# DONGLE01.net
KiCad netlist of a schematic drawn in Altium Designer
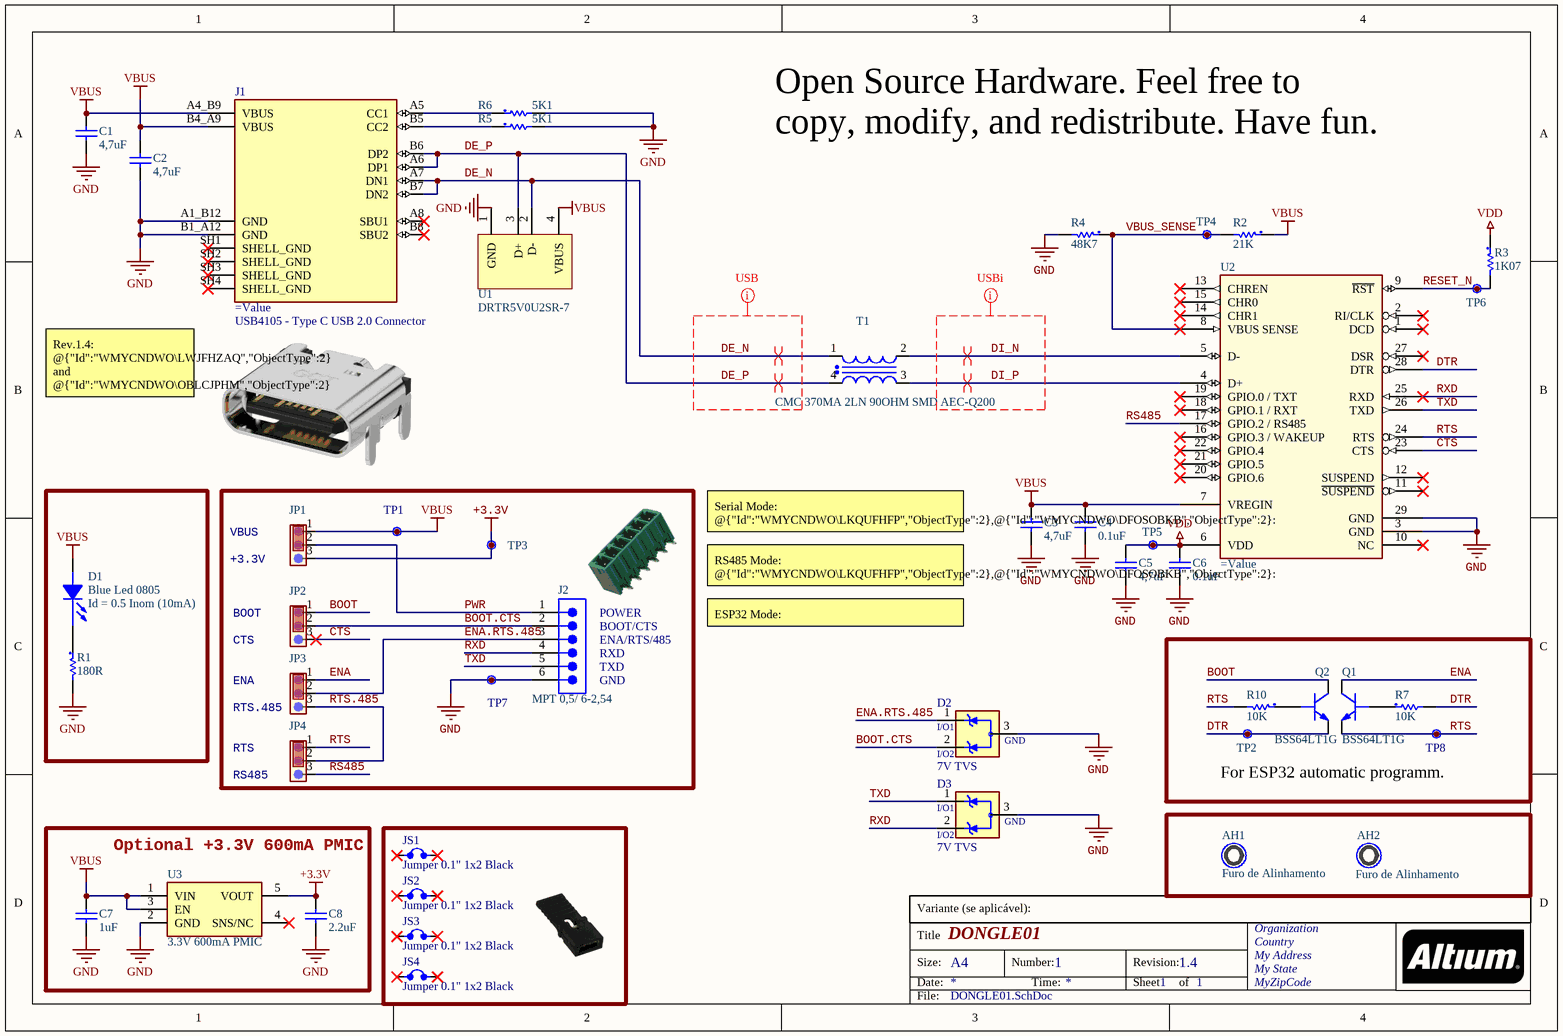
[diagram p0: DONGLE01.SchDoc]

(export (version "E")
  (design (tool "Eeschema 10.0.6"))
  (components
    (comp (ref "AH1")
      (value "Furo de Alinhamento")
      (footprint "AH_2.0MMD")
      (libsource (lib "My_Library") (part "Aligment Hole M2"))
    )
    (comp (ref "AH2")
      (value "Furo de Alinhamento")
      (footprint "AH_2.0MMD")
      (libsource (lib "My_Library") (part "Aligment Hole M2"))
    )
    (comp (ref "C1")
      (value "4,7uF")
      (footprint "C0805")
      (description "4.7 µF ±5% 25V Capacitor de cerâmica X7R 0805 (métrico 2012)")
      (fields (field (name "MANUFACTURER") "KEMET"))
      (libsource (lib "My_Library") (part "CAP"))
    )
    (comp (ref "C2")
      (value "4,7uF")
      (footprint "C0805")
      (description "4.7 µF ±5% 25V Capacitor de cerâmica X7R 0805 (métrico 2012)")
      (fields (field (name "MANUFACTURER") "KEMET"))
      (libsource (lib "My_Library") (part "CAP"))
    )
    (comp (ref "C3")
      (value "4,7uF")
      (footprint "C0805")
      (description "4.7 µF ±5% 25V Capacitor de cerâmica X7R 0805 (métrico 2012)")
      (fields (field (name "MANUFACTURER") "KEMET"))
      (libsource (lib "My_Library") (part "CAP"))
    )
    (comp (ref "C4")
      (value "0.1uF")
      (footprint "C0805")
      (description "0.1 µF ±10% 100V Ceramic Capacitor X7R 0805 (2012 Metric)")
      (fields (field (name "MANUFACTURER") "Murata Electronics"))
      (libsource (lib "My_Library") (part "CAP"))
    )
    (comp (ref "C5")
      (value "4,7uF")
      (footprint "C0805")
      (description "4.7 µF ±5% 25V Capacitor de cerâmica X7R 0805 (métrico 2012)")
      (fields (field (name "MANUFACTURER") "KEMET"))
      (libsource (lib "My_Library") (part "CAP"))
    )
    (comp (ref "C6")
      (value "0.1uF")
      (footprint "C0805")
      (description "0.1 µF ±10% 100V Ceramic Capacitor X7R 0805 (2012 Metric)")
      (fields (field (name "MANUFACTURER") "Murata Electronics"))
      (libsource (lib "My_Library") (part "CAP"))
    )
    (comp (ref "C7")
      (value "1uF")
      (footprint "C0805")
      (description "1 µF ±5% 16V Ceramic Capacitor X7R 0805 (2012 Metric)")
      (fields (field (name "MANUFACTURER") "KEMET"))
      (libsource (lib "My_Library") (part "CAP"))
    )
    (comp (ref "C8")
      (value "2.2uF")
      (footprint "C0805")
      (description "2.2 µF ±5% 16V Ceramic Capacitor X7R 0805 (2012 Metric)")
      (fields (field (name "MANUFACTURER") "KEMET"))
      (libsource (lib "My_Library") (part "CAP"))
    )
    (comp (ref "D1")
      (value "Blue Led 0805")
      (footprint "LED 0805")
      (description "Blue 470nm LED Indication - Discrete 3.2V 0805 (2012 Metric)")
      (fields (field (name "MANUFACTURER") "Würth Elektronik") (field (name "INFO") "Id = 0.5 Inom (10mA)"))
      (libsource (lib "My_Library") (part "LED GREEN 0805"))
    )
    (comp (ref "D2")
      (value "7V TVS")
      (footprint "WE-TVS_SOT23-3L")
      (description "7V Clamp 15A (8/20µs) Ipp Tvs Diode Surface Mount SOT-23-3")
      (fields (field (name "MANUFACTURER") "Würth Elektronik"))
      (libsource (lib "My_Library") (part "WE-TVS_SOT23-3L_824021"))
    )
    (comp (ref "D3")
      (value "7V TVS")
      (footprint "WE-TVS_SOT23-3L")
      (description "7V Clamp 15A (8/20µs) Ipp Tvs Diode Surface Mount SOT-23-3")
      (fields (field (name "MANUFACTURER") "Würth Elektronik"))
      (libsource (lib "My_Library") (part "WE-TVS_SOT23-3L_824021"))
    )
    (comp (ref "J1")
      (value "~")
      (footprint "GCT_USB4105-GF-A-060")
      (fields
        (field (name "INFO") "USB4105 - Type C USB 2.0 Connector")
        (field (name "MANUFACTURER") "Global Connector Technology")
      )
      (libsource (lib "My_Library") (part "USB4105-GF-A-060"))
    )
    (comp (ref "J2")
      (value "MPT 0,5/ 6-2,54")
      (footprint "1725698")
      (description "6 Position Wire to Board Terminal Block Horizontal with Board 0.100\" (2.54mm) Through Hole")
      (fields (field (name "MANUFACTURER") "Phoenix Contact"))
      (libsource (lib "691101710002_Altium_WR-TBL_rev23c") (part "691322110006"))
    )
    (comp (ref "JP1")
      (value "Header 3 Pin")
      (footprint "JMP-3-PTH-180")
      (description "3 Pin Jumper")
      (fields (field (name "MANUFACTURER") "Würth Elektronik"))
      (libsource (lib "My_Library") (part "Jumper 3"))
    )
    (comp (ref "JP2")
      (value "Header 3 Pin")
      (footprint "JMP-3-PTH-180")
      (description "3 Pin Jumper")
      (fields (field (name "MANUFACTURER") "Würth Elektronik"))
      (libsource (lib "My_Library") (part "Jumper 3"))
    )
    (comp (ref "JP3")
      (value "Header 3 Pin")
      (footprint "JMP-3-PTH-180")
      (description "3 Pin Jumper")
      (fields (field (name "MANUFACTURER") "Würth Elektronik"))
      (libsource (lib "My_Library") (part "Jumper 3"))
    )
    (comp (ref "JP4")
      (value "Header 3 Pin")
      (footprint "JMP-3-PTH-180")
      (description "3 Pin Jumper")
      (fields (field (name "MANUFACTURER") "Würth Elektronik"))
      (libsource (lib "My_Library") (part "Jumper 3"))
    )
    (comp (ref "JS1")
      (value "Jumper 0.1\" 1x2 Black")
      (description "2 (1 x 2) Position Shunt Connector Open Top, Grip 0.100\" (2.54mm) Gold")
      (fields (field (name "MANUFACTURER") "Sullins Connector Solutions"))
      (libsource (lib "My_Library") (part "Jumper 2"))
    )
    (comp (ref "JS2")
      (value "Jumper 0.1\" 1x2 Black")
      (description "2 (1 x 2) Position Shunt Connector Open Top, Grip 0.100\" (2.54mm) Gold")
      (fields (field (name "MANUFACTURER") "Sullins Connector Solutions"))
      (libsource (lib "My_Library") (part "Jumper 2"))
    )
    (comp (ref "JS3")
      (value "Jumper 0.1\" 1x2 Black")
      (description "2 (1 x 2) Position Shunt Connector Open Top, Grip 0.100\" (2.54mm) Gold")
      (fields (field (name "MANUFACTURER") "Sullins Connector Solutions"))
      (libsource (lib "My_Library") (part "Jumper 2"))
    )
    (comp (ref "JS4")
      (value "Jumper 0.1\" 1x2 Black")
      (description "2 (1 x 2) Position Shunt Connector Open Top, Grip 0.100\" (2.54mm) Gold")
      (fields (field (name "MANUFACTURER") "Sullins Connector Solutions"))
      (libsource (lib "My_Library") (part "Jumper 2"))
    )
    (comp (ref "Q1")
      (value "BSS64LT1G")
      (footprint "SOT-23")
      (description "Bipolar (BJT) Transistor NPN 80 V 100 mA 60MHz 225 mW Surface Mount SOT-23-3 (TO-236)")
      (fields (field (name "MANUFACTURER") "onsemi"))
      (libsource (lib "My_Library") (part "TR-NPN-BC817-SOT23"))
    )
    (comp (ref "Q2")
      (value "BSS64LT1G")
      (footprint "SOT-23")
      (description "Bipolar (BJT) Transistor NPN 80 V 100 mA 60MHz 225 mW Surface Mount SOT-23-3 (TO-236)")
      (fields (field (name "MANUFACTURER") "onsemi"))
      (libsource (lib "My_Library") (part "TR-NPN-BC817-SOT23"))
    )
    (comp (ref "R1")
      (value "180R")
      (footprint "R0805")
      (description "180 Ohms ±1% 0.25W, 1/4W Chip Resistor 0805 (2012 Metric) Anti-Sulfur Thin Film")
      (fields (field (name "MANUFACTURER") "Stackpole Electronics Inc"))
      (libsource (lib "My_Library") (part "RESISTOR"))
    )
    (comp (ref "R2")
      (value "21K")
      (footprint "R0805")
      (description "21 kOhms ±1% 0.125W, 1/8W Chip Resistor 0805 (2012 Metric) Moisture Resistant Thick Film")
      (fields (field (name "MANUFACTURER") "YAGEO"))
      (libsource (lib "My_Library") (part "RESISTOR"))
    )
    (comp (ref "R3")
      (value "1K07")
      (footprint "R0805")
      (description "1.07 kOhms ±1% 0.125W, 1/8W Chip Resistor 0805 (2012 Metric) Automotive AEC-Q200 Thick Film")
      (fields (field (name "MANUFACTURER") "Vishay Dale"))
      (libsource (lib "My_Library") (part "RESISTOR"))
    )
    (comp (ref "R4")
      (value "48K7")
      (footprint "R0805")
      (description "48.7 kOhms ±1% 0.125W, 1/8W Chip Resistor 0805 (2012 Metric) Moisture Resistant Thick Film")
      (fields (field (name "MANUFACTURER") "YAGEO"))
      (libsource (lib "My_Library") (part "RESISTOR"))
    )
    (comp (ref "R5")
      (value "5K1")
      (footprint "R0805")
      (description "5.1 kOhms ±1% 0.125W, 1/8W Chip Resistor 0805 (2012 Metric) Moisture Resistant Thick Film")
      (fields (field (name "MANUFACTURER") "YAGEO"))
      (libsource (lib "My_Library") (part "RESISTOR"))
    )
    (comp (ref "R6")
      (value "5K1")
      (footprint "R0805")
      (description "5.1 kOhms ±1% 0.125W, 1/8W Chip Resistor 0805 (2012 Metric) Moisture Resistant Thick Film")
      (fields (field (name "MANUFACTURER") "YAGEO"))
      (libsource (lib "My_Library") (part "RESISTOR"))
    )
    (comp (ref "R7")
      (value "10K")
      (footprint "R0805")
      (description "10 kOhms ±1% 0.125W, 1/8W Chip Resistor 0805 (2012 Metric) Automotive AEC-Q200 Thick Film")
      (fields (field (name "MANUFACTURER") "Stackpole Electronics Inc"))
      (libsource (lib "My_Library") (part "RESISTOR"))
    )
    (comp (ref "R10")
      (value "10K")
      (footprint "R0805")
      (description "10 kOhms ±1% 0.125W, 1/8W Chip Resistor 0805 (2012 Metric) Automotive AEC-Q200 Thick Film")
      (fields (field (name "MANUFACTURER") "Stackpole Electronics Inc"))
      (libsource (lib "My_Library") (part "RESISTOR"))
    )
    (comp (ref "T1")
      (value "CMC 370MA 2LN 90OHM SMD AEC-Q200")
      (footprint "744232090")
      (description "2 Line Common Mode Choke Surface Mount 90 Ohms @ 100 MHz 370mA DCR 300mOhm")
      (fields (field (name "MANUFACTURER") "Würth Elektronik"))
      (libsource (lib "My_Library") (part "USB EMI FILTER"))
    )
    (comp (ref "TP1") (value "~") (footprint "TP") (libsource (lib "My_Library") (part "TESTPOINT")))
    (comp (ref "TP2") (value "~") (footprint "TP") (libsource (lib "My_Library") (part "TESTPOINT")))
    (comp (ref "TP3") (value "~") (footprint "TP") (libsource (lib "My_Library") (part "TESTPOINT")))
    (comp (ref "TP4") (value "~") (footprint "TP") (libsource (lib "My_Library") (part "TESTPOINT")))
    (comp (ref "TP5") (value "~") (footprint "TP") (libsource (lib "My_Library") (part "TESTPOINT")))
    (comp (ref "TP6") (value "~") (footprint "TP") (libsource (lib "My_Library") (part "TESTPOINT")))
    (comp (ref "TP7") (value "~") (footprint "TP") (libsource (lib "My_Library") (part "TESTPOINT")))
    (comp (ref "TP8") (value "~") (footprint "TP") (libsource (lib "My_Library") (part "TESTPOINT")))
    (comp (ref "U1")
      (value "USB ESD protection")
      (footprint "SOT143-4")
      (description "Clamp Ipp Tvs Diode Surface Mount SOT-143")
      (fields
        (field (name "MANUFACTURER P/N") "DRTR5V0U2SR-7")
        (field (name "MANUFACTURER") "Diodes Incorporated")
      )
      (libsource (lib "My_Library") (part "USB2.0_TVS_DIODES"))
    )
    (comp (ref "U2")
      (value "~")
      (footprint "QFN50P500X500X80_HS-29N CP2102N")
      (description "USB Bridge, USB to UART USB 2.0 UART Interface 28-QFN (5x5)")
      (fields (field (name "MANUFACTURER") "Silicon Labs"))
      (libsource (lib "My_Library") (part "CP2102N QFN28"))
    )
    (comp (ref "U3")
      (value "3.3V 600mA PMIC")
      (footprint "SOT94P280X100-5N")
      (description "Linear Voltage Regulator IC Positive Fixed 1 Output 600mA TSOT-23-5")
      (fields (field (name "MANUFACTURER") "Richtek USA Inc."))
      (libsource (lib "*") (part "RT9080-33GJ5"))
    )
  )
  (nets
    (net (code "1") (name "+3.3V") (class "Default")
      (node (ref "C8") (pin "1") (pinfunction "1_1") (pintype "passive"))
      (node (ref "JP1") (pin "3") (pinfunction "3_3") (pintype "passive"))
      (node (ref "TP3") (pin "1") (pinfunction "A_1") (pintype "passive"))
      (node (ref "U3") (pin "5") (pinfunction "VOUT_5") (pintype "power_in"))
    )
    (net (code "2") (name "/BOOT") (class "Default")
      (node (ref "JP2") (pin "1") (pinfunction "1_1") (pintype "passive"))
      (node (ref "Q2") (pin "3") (pinfunction "C_3") (pintype "passive"))
    )
    (net (code "3") (name "/BOOT.CTS") (class "Default")
      (node (ref "D2") (pin "2") (pinfunction "I/O2_2") (pintype "passive"))
      (node (ref "J2") (pin "2") (pinfunction "2_2") (pintype "passive"))
      (node (ref "JP2") (pin "2") (pinfunction "2_2") (pintype "passive"))
    )
    (net (code "4") (name "/CTS") (class "Default")
      (node (ref "JP2") (pin "3") (pinfunction "3_3") (pintype "passive"))
      (node (ref "U2") (pin "23") (pinfunction "CTS_23") (pintype "input"))
    )
    (net (code "5") (name "/DE_N") (class "Default")
      (node (ref "J1") (pin "A7") (pinfunction "DN1_A7") (pintype "bidirectional"))
      (node (ref "J1") (pin "B7") (pinfunction "DN2_B7") (pintype "bidirectional"))
      (node (ref "T1") (pin "1") (pinfunction "1_1") (pintype "passive"))
      (node (ref "U1") (pin "2") (pinfunction "D-_2") (pintype "passive"))
    )
    (net (code "6") (name "/DE_P") (class "Default")
      (node (ref "J1") (pin "A6") (pinfunction "DP1_A6") (pintype "bidirectional"))
      (node (ref "J1") (pin "B6") (pinfunction "DP2_B6") (pintype "bidirectional"))
      (node (ref "T1") (pin "4") (pinfunction "4_4") (pintype "passive"))
      (node (ref "U1") (pin "3") (pinfunction "D+_3") (pintype "passive"))
    )
    (net (code "7") (name "/DI_N") (class "Default")
      (node (ref "T1") (pin "2") (pinfunction "2_2") (pintype "passive"))
      (node (ref "U2") (pin "5") (pinfunction "D-_5") (pintype "bidirectional"))
    )
    (net (code "8") (name "/DI_P") (class "Default")
      (node (ref "T1") (pin "3") (pinfunction "3_3") (pintype "passive"))
      (node (ref "U2") (pin "4") (pinfunction "D+_4") (pintype "bidirectional"))
    )
    (net (code "9") (name "/DTR") (class "Default")
      (node (ref "Q2") (pin "2") (pinfunction "E_2") (pintype "passive"))
      (node (ref "R7") (pin "2") (pinfunction "2_2") (pintype "passive"))
      (node (ref "TP2") (pin "1") (pinfunction "A_1") (pintype "passive"))
      (node (ref "U2") (pin "28") (pinfunction "DTR_28") (pintype "output"))
    )
    (net (code "10") (name "/ENA") (class "Default")
      (node (ref "JP3") (pin "1") (pinfunction "1_1") (pintype "passive"))
      (node (ref "Q1") (pin "3") (pinfunction "C_3") (pintype "passive"))
    )
    (net (code "11") (name "/ENA.RTS.485") (class "Default")
      (node (ref "D2") (pin "1") (pinfunction "I/O1_1") (pintype "passive"))
      (node (ref "J2") (pin "3") (pinfunction "3_3") (pintype "passive"))
      (node (ref "JP3") (pin "2") (pinfunction "2_2") (pintype "passive"))
    )
    (net (code "12") (name "/PWR") (class "Default")
      (node (ref "J2") (pin "1") (pinfunction "1_1") (pintype "passive"))
      (node (ref "JP1") (pin "2") (pinfunction "2_2") (pintype "passive"))
    )
    (net (code "13") (name "/RESET_N") (class "Default")
      (node (ref "R3") (pin "2") (pinfunction "2_2") (pintype "passive"))
      (node (ref "TP6") (pin "1") (pinfunction "A_1") (pintype "passive"))
      (node (ref "U2") (pin "9") (pinfunction "~{RST}_9") (pintype "bidirectional"))
    )
    (net (code "14") (name "/RS485") (class "Default")
      (node (ref "JP4") (pin "3") (pinfunction "3_3") (pintype "passive"))
      (node (ref "U2") (pin "17") (pinfunction "GPIO.2_/_RS485_17") (pintype "bidirectional"))
    )
    (net (code "15") (name "/RTS") (class "Default")
      (node (ref "JP4") (pin "1") (pinfunction "1_1") (pintype "passive"))
      (node (ref "Q1") (pin "2") (pinfunction "E_2") (pintype "passive"))
      (node (ref "R10") (pin "2") (pinfunction "2_2") (pintype "passive"))
      (node (ref "TP8") (pin "1") (pinfunction "A_1") (pintype "passive"))
      (node (ref "U2") (pin "24") (pinfunction "RTS_24") (pintype "output"))
    )
    (net (code "16") (name "/RTS.485") (class "Default")
      (node (ref "JP3") (pin "3") (pinfunction "3_3") (pintype "passive"))
      (node (ref "JP4") (pin "2") (pinfunction "2_2") (pintype "passive"))
    )
    (net (code "17") (name "/RXD") (class "Default")
      (node (ref "D3") (pin "2") (pinfunction "I/O2_2") (pintype "passive"))
      (node (ref "J2") (pin "4") (pinfunction "4_4") (pintype "passive"))
      (node (ref "U2") (pin "25") (pinfunction "RXD_25") (pintype "input"))
    )
    (net (code "18") (name "/TXD") (class "Default")
      (node (ref "D3") (pin "1") (pinfunction "I/O1_1") (pintype "passive"))
      (node (ref "J2") (pin "5") (pinfunction "5_5") (pintype "passive"))
      (node (ref "U2") (pin "26") (pinfunction "TXD_26") (pintype "output"))
    )
    (net (code "19") (name "/VBUS_SENSE") (class "Default")
      (node (ref "R2") (pin "2") (pinfunction "2_2") (pintype "passive"))
      (node (ref "R4") (pin "1") (pinfunction "1_1") (pintype "passive"))
      (node (ref "TP4") (pin "1") (pinfunction "A_1") (pintype "passive"))
      (node (ref "U2") (pin "8") (pinfunction "VBUS_SENSE_8") (pintype "input"))
    )
    (net (code "20") (name "GND") (class "Default")
      (node (ref "C1") (pin "2") (pinfunction "2_2") (pintype "passive"))
      (node (ref "C2") (pin "2") (pinfunction "2_2") (pintype "passive"))
      (node (ref "C3") (pin "2") (pinfunction "2_2") (pintype "passive"))
      (node (ref "C4") (pin "2") (pinfunction "2_2") (pintype "passive"))
      (node (ref "C5") (pin "2") (pinfunction "2_2") (pintype "passive"))
      (node (ref "C6") (pin "2") (pinfunction "2_2") (pintype "passive"))
      (node (ref "C7") (pin "2") (pinfunction "2_2") (pintype "passive"))
      (node (ref "C8") (pin "2") (pinfunction "2_2") (pintype "passive"))
      (node (ref "D2") (pin "3") (pinfunction "GND_3") (pintype "passive"))
      (node (ref "D3") (pin "3") (pinfunction "GND_3") (pintype "passive"))
      (node (ref "J1") (pin "A1_B12") (pinfunction "GND_A1_B12") (pintype "power_in"))
      (node (ref "J1") (pin "B1_A12") (pinfunction "GND_B1_A12") (pintype "power_in"))
      (node (ref "J2") (pin "6") (pinfunction "6_6") (pintype "passive"))
      (node (ref "R1") (pin "2") (pinfunction "2_2") (pintype "passive"))
      (node (ref "R4") (pin "2") (pinfunction "2_2") (pintype "passive"))
      (node (ref "R5") (pin "2") (pinfunction "2_2") (pintype "passive"))
      (node (ref "R6") (pin "2") (pinfunction "2_2") (pintype "passive"))
      (node (ref "TP7") (pin "1") (pinfunction "A_1") (pintype "passive"))
      (node (ref "U1") (pin "1") (pinfunction "GND_1") (pintype "power_in"))
      (node (ref "U2") (pin "29") (pinfunction "GND_29") (pintype "power_in"))
      (node (ref "U2") (pin "3") (pinfunction "GND_3") (pintype "power_in"))
      (node (ref "U3") (pin "2") (pinfunction "GND_2") (pintype "power_in"))
    )
    (net (code "21") (name "Net-(D1-PadK)") (class "Default")
      (node (ref "D1") (pin "K") (pinfunction "K_K") (pintype "passive"))
      (node (ref "R1") (pin "1") (pinfunction "1_1") (pintype "passive"))
    )
    (net (code "22") (name "Net-(J1-CC1)") (class "Default")
      (node (ref "J1") (pin "A5") (pinfunction "CC1_A5") (pintype "bidirectional"))
      (node (ref "R6") (pin "1") (pinfunction "1_1") (pintype "passive"))
    )
    (net (code "23") (name "Net-(J1-CC2)") (class "Default")
      (node (ref "J1") (pin "B5") (pinfunction "CC2_B5") (pintype "bidirectional"))
      (node (ref "R5") (pin "1") (pinfunction "1_1") (pintype "passive"))
    )
    (net (code "24") (name "Net-(Q1-B)") (class "Default")
      (node (ref "Q1") (pin "1") (pinfunction "B_1") (pintype "passive"))
      (node (ref "R7") (pin "1") (pinfunction "1_1") (pintype "passive"))
    )
    (net (code "25") (name "Net-(Q2-B)") (class "Default")
      (node (ref "Q2") (pin "1") (pinfunction "B_1") (pintype "passive"))
      (node (ref "R10") (pin "1") (pinfunction "1_1") (pintype "passive"))
    )
    (net (code "26") (name "VBUS") (class "Default")
      (node (ref "C1") (pin "1") (pinfunction "1_1") (pintype "passive"))
      (node (ref "C2") (pin "1") (pinfunction "1_1") (pintype "passive"))
      (node (ref "C3") (pin "1") (pinfunction "1_1") (pintype "passive"))
      (node (ref "C4") (pin "1") (pinfunction "1_1") (pintype "passive"))
      (node (ref "C7") (pin "1") (pinfunction "1_1") (pintype "passive"))
      (node (ref "D1") (pin "A") (pinfunction "A_A") (pintype "passive"))
      (node (ref "J1") (pin "A4_B9") (pinfunction "VBUS_A4_B9") (pintype "power_in"))
      (node (ref "J1") (pin "B4_A9") (pinfunction "VBUS_B4_A9") (pintype "power_in"))
      (node (ref "JP1") (pin "1") (pinfunction "1_1") (pintype "passive"))
      (node (ref "R2") (pin "1") (pinfunction "1_1") (pintype "passive"))
      (node (ref "TP1") (pin "1") (pinfunction "A_1") (pintype "passive"))
      (node (ref "U1") (pin "4") (pinfunction "VBUS_4") (pintype "power_in"))
      (node (ref "U2") (pin "7") (pinfunction "VREGIN_7") (pintype "power_in"))
      (node (ref "U3") (pin "1") (pinfunction "VIN_1") (pintype "power_in"))
      (node (ref "U3") (pin "3") (pinfunction "EN_3") (pintype "passive"))
    )
    (net (code "27") (name "VDD") (class "Default")
      (node (ref "C5") (pin "1") (pinfunction "1_1") (pintype "passive"))
      (node (ref "C6") (pin "1") (pinfunction "1_1") (pintype "passive"))
      (node (ref "R3") (pin "1") (pinfunction "1_1") (pintype "passive"))
      (node (ref "TP5") (pin "1") (pinfunction "A_1") (pintype "passive"))
      (node (ref "U2") (pin "6") (pinfunction "VDD_6") (pintype "power_in"))
    )
    (net (code "28") (name "unconnected-(J1-SBU1-PadA8)") (class "Default")
      (node (ref "J1") (pin "A8") (pinfunction "SBU1_A8") (pintype "bidirectional+no_connect"))
    )
    (net (code "29") (name "unconnected-(J1-SBU2-PadB8)") (class "Default")
      (node (ref "J1") (pin "B8") (pinfunction "SBU2_B8") (pintype "bidirectional+no_connect"))
    )
    (net (code "30") (name "unconnected-(J1-SHELL_GND-PadSH1)") (class "Default")
      (node (ref "J1") (pin "SH1") (pinfunction "SHELL_GND_SH1") (pintype "power_in+no_connect"))
    )
    (net (code "31") (name "unconnected-(J1-SHELL_GND-PadSH2)") (class "Default")
      (node (ref "J1") (pin "SH2") (pinfunction "SHELL_GND_SH2") (pintype "power_in+no_connect"))
    )
    (net (code "32") (name "unconnected-(J1-SHELL_GND-PadSH3)") (class "Default")
      (node (ref "J1") (pin "SH3") (pinfunction "SHELL_GND_SH3") (pintype "power_in+no_connect"))
    )
    (net (code "33") (name "unconnected-(J1-SHELL_GND-PadSH4)") (class "Default")
      (node (ref "J1") (pin "SH4") (pinfunction "SHELL_GND_SH4") (pintype "power_in+no_connect"))
    )
    (net (code "34") (name "unconnected-(JS1-Pad1)") (class "Default")
      (node (ref "JS1") (pin "1") (pinfunction "1_1") (pintype "passive+no_connect"))
    )
    (net (code "35") (name "unconnected-(JS1-Pad2)") (class "Default")
      (node (ref "JS1") (pin "2") (pinfunction "2_2") (pintype "passive+no_connect"))
    )
    (net (code "36") (name "unconnected-(JS2-Pad1)") (class "Default")
      (node (ref "JS2") (pin "1") (pinfunction "1_1") (pintype "passive+no_connect"))
    )
    (net (code "37") (name "unconnected-(JS2-Pad2)") (class "Default")
      (node (ref "JS2") (pin "2") (pinfunction "2_2") (pintype "passive+no_connect"))
    )
    (net (code "38") (name "unconnected-(JS3-Pad1)") (class "Default")
      (node (ref "JS3") (pin "1") (pinfunction "1_1") (pintype "passive+no_connect"))
    )
    (net (code "39") (name "unconnected-(JS3-Pad2)") (class "Default")
      (node (ref "JS3") (pin "2") (pinfunction "2_2") (pintype "passive+no_connect"))
    )
    (net (code "40") (name "unconnected-(JS4-Pad1)") (class "Default")
      (node (ref "JS4") (pin "1") (pinfunction "1_1") (pintype "passive+no_connect"))
    )
    (net (code "41") (name "unconnected-(JS4-Pad2)") (class "Default")
      (node (ref "JS4") (pin "2") (pinfunction "2_2") (pintype "passive+no_connect"))
    )
    (net (code "42") (name "unconnected-(U2-CHR0-Pad15)") (class "Default")
      (node (ref "U2") (pin "15") (pinfunction "CHR0_15") (pintype "output+no_connect"))
    )
    (net (code "43") (name "unconnected-(U2-CHR1-Pad14)") (class "Default")
      (node (ref "U2") (pin "14") (pinfunction "CHR1_14") (pintype "output+no_connect"))
    )
    (net (code "44") (name "unconnected-(U2-CHREN-Pad13)") (class "Default")
      (node (ref "U2") (pin "13") (pinfunction "CHREN_13") (pintype "output+no_connect"))
    )
    (net (code "45") (name "unconnected-(U2-DCD-Pad1)") (class "Default")
      (node (ref "U2") (pin "1") (pinfunction "DCD_1") (pintype "input+no_connect"))
    )
    (net (code "46") (name "unconnected-(U2-DSR-Pad27)") (class "Default")
      (node (ref "U2") (pin "27") (pinfunction "DSR_27") (pintype "input+no_connect"))
    )
    (net (code "47") (name "unconnected-(U2-GPIO.0_{slash}_TXT-Pad19)") (class "Default")
      (node (ref "U2") (pin "19") (pinfunction "GPIO.0_/_TXT_19") (pintype "bidirectional+no_connect"))
    )
    (net (code "48") (name "unconnected-(U2-GPIO.1_{slash}_RXT-Pad18)") (class "Default")
      (node (ref "U2") (pin "18") (pinfunction "GPIO.1_/_RXT_18") (pintype "bidirectional+no_connect"))
    )
    (net (code "49") (name "unconnected-(U2-GPIO.3_{slash}_WAKEUP-Pad16)") (class "Default")
      (node (ref "U2") (pin "16") (pinfunction "GPIO.3_/_WAKEUP_16") (pintype "bidirectional+no_connect"))
    )
    (net (code "50") (name "unconnected-(U2-GPIO.4-Pad22)") (class "Default")
      (node (ref "U2") (pin "22") (pinfunction "GPIO.4_22") (pintype "bidirectional+no_connect"))
    )
    (net (code "51") (name "unconnected-(U2-GPIO.5-Pad21)") (class "Default")
      (node (ref "U2") (pin "21") (pinfunction "GPIO.5_21") (pintype "bidirectional+no_connect"))
    )
    (net (code "52") (name "unconnected-(U2-GPIO.6-Pad20)") (class "Default")
      (node (ref "U2") (pin "20") (pinfunction "GPIO.6_20") (pintype "bidirectional+no_connect"))
    )
    (net (code "53") (name "unconnected-(U2-NC-Pad10)") (class "Default")
      (node (ref "U2") (pin "10") (pinfunction "NC_10") (pintype "passive+no_connect"))
    )
    (net (code "54") (name "unconnected-(U2-RI{slash}CLK-Pad2)") (class "Default")
      (node (ref "U2") (pin "2") (pinfunction "RI/CLK_2") (pintype "input+no_connect"))
    )
    (net (code "55") (name "unconnected-(U2-SUSPEND-Pad12)") (class "Default")
      (node (ref "U2") (pin "12") (pinfunction "SUSPEND_12") (pintype "output+no_connect"))
    )
    (net (code "56") (name "unconnected-(U2-~{SUSPEND}-Pad11)") (class "Default")
      (node (ref "U2") (pin "11") (pinfunction "~{SUSPEND}_11") (pintype "output+no_connect"))
    )
    (net (code "57") (name "unconnected-(U3-SNS{slash}NC-Pad4)") (class "Default")
      (node (ref "U3") (pin "4") (pinfunction "SNS/NC_4") (pintype "passive+no_connect"))
    )
  )
)
